# con-right-bot.net
KiCad netlist of a schematic drawn in Altium Designer
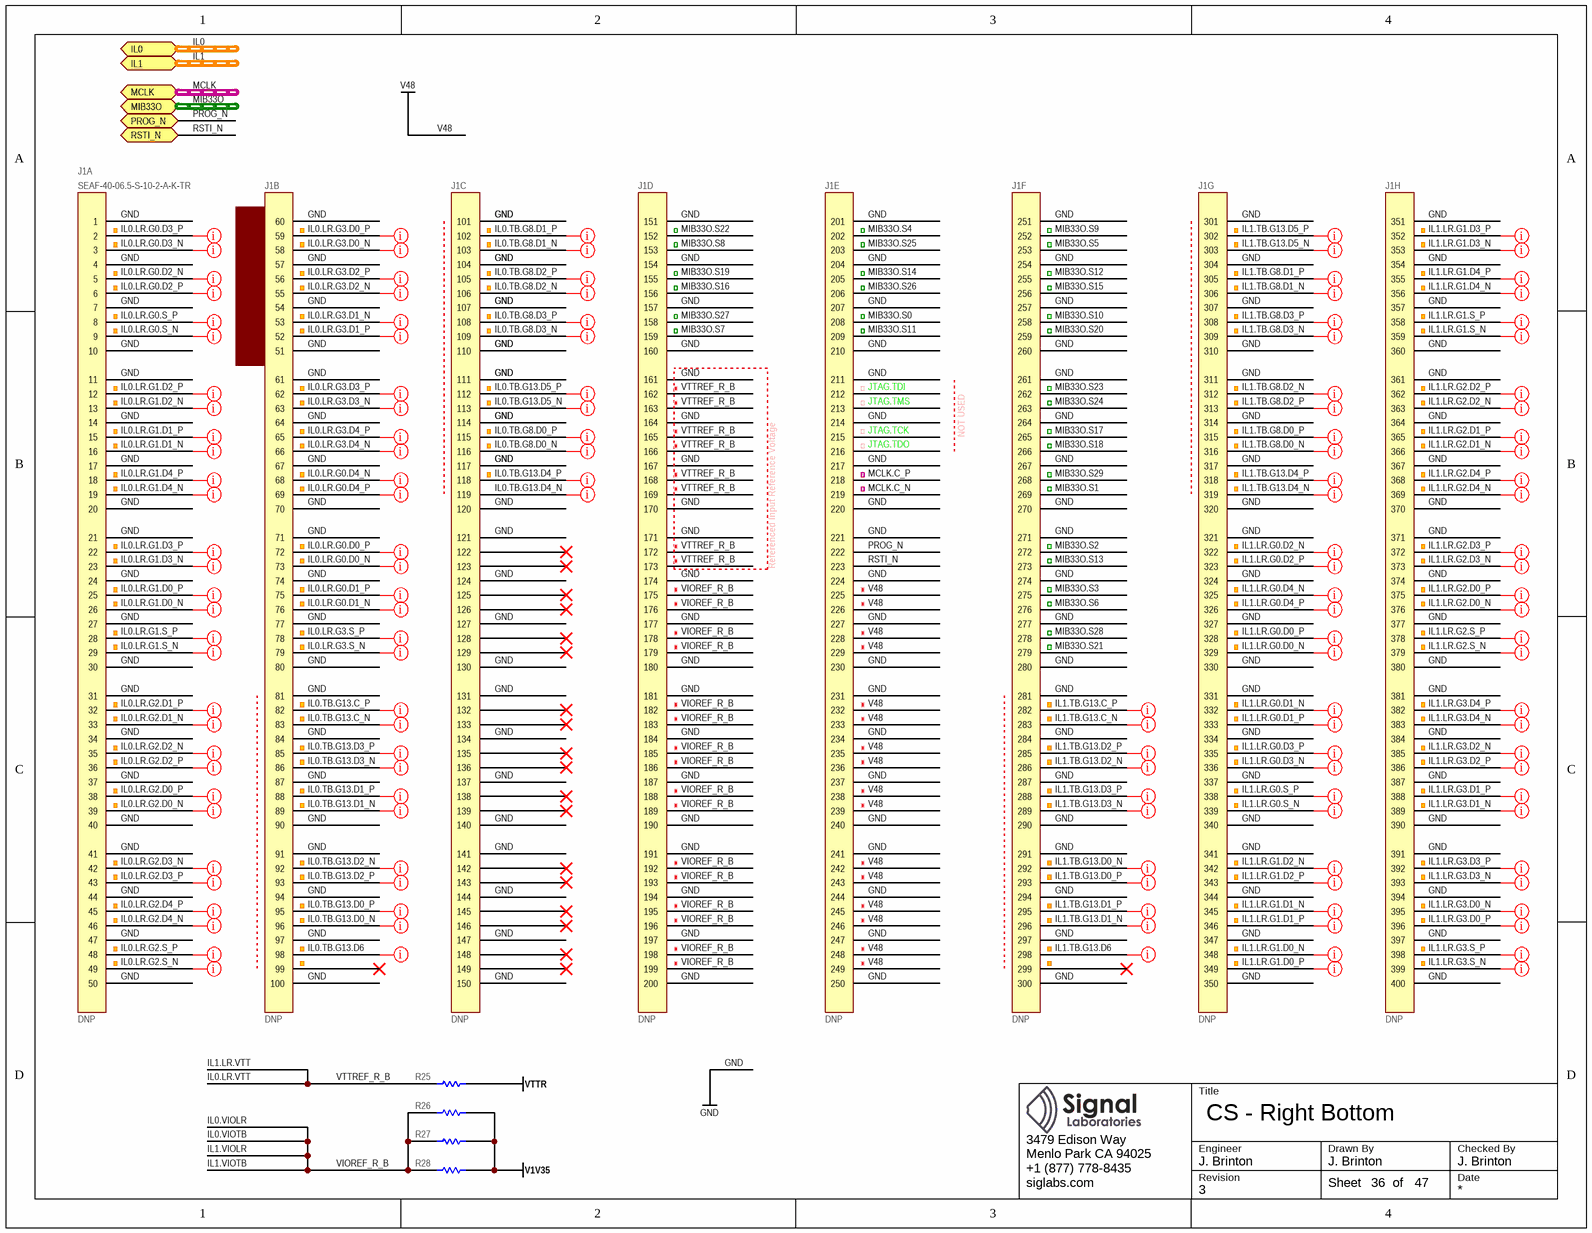
[diagram p0: con-right-bot.SchDoc]

(export (version "E")
  (design (tool "Eeschema 10.0.6"))
  (components
    (comp (ref "J1")
      (value "SEAF-40-06.5-S-10-2-A-K-TR")
      (footprint "samtec:SEAF-40-06.5-S-10-2-A-K-TR")
      (description "Terminal Array Assembly, Surface Mount, 0.050\" Pitch, 400 Pins")
      (fields (field (name "MANUFACTURER") "Samtec") (field (name "DO NOT PLACE") "DNP"))
      (libsource (lib "samtec") (part "SEAF-40-06.5-S-10-2-A-K-TR"))
    )
    (comp (ref "R25")
      (value "SOLDER_LINK")
      (footprint "SOLDERLINK0603X26N")
      (description "Solder Link")
      (libsource (lib "generic") (part "RES"))
    )
    (comp (ref "R26")
      (value "SOLDER_LINK")
      (footprint "SOLDERLINK0603X26N")
      (description "Solder Link")
      (libsource (lib "generic") (part "RES"))
    )
    (comp (ref "R27")
      (value "SOLDER_LINK")
      (footprint "SOLDERLINK0603X26N")
      (description "Solder Link")
      (libsource (lib "generic") (part "RES"))
    )
    (comp (ref "R28")
      (value "SOLDER_LINK")
      (footprint "SOLDERLINK0603X26N")
      (description "Solder Link")
      (libsource (lib "generic") (part "RES"))
    )
  )
  (nets
    (net (code "5") (name "/IL0.LR.G0.D0_N") (class "Default")
      (node (ref "J1") (pin "73") (pinfunction "73_73") (pintype "passive"))
    )
    (net (code "6") (name "/IL0.LR.G0.D0_P") (class "Default")
      (node (ref "J1") (pin "72") (pinfunction "72_72") (pintype "passive"))
    )
    (net (code "7") (name "/IL0.LR.G0.D1_N") (class "Default")
      (node (ref "J1") (pin "76") (pinfunction "76_76") (pintype "passive"))
    )
    (net (code "8") (name "/IL0.LR.G0.D1_P") (class "Default")
      (node (ref "J1") (pin "75") (pinfunction "75_75") (pintype "passive"))
    )
    (net (code "9") (name "/IL0.LR.G0.D2_N") (class "Default")
      (node (ref "J1") (pin "5") (pinfunction "5_5") (pintype "passive"))
    )
    (net (code "10") (name "/IL0.LR.G0.D2_P") (class "Default")
      (node (ref "J1") (pin "6") (pinfunction "6_6") (pintype "passive"))
    )
    (net (code "11") (name "/IL0.LR.G0.D3_N") (class "Default")
      (node (ref "J1") (pin "3") (pinfunction "3_3") (pintype "passive"))
    )
    (net (code "12") (name "/IL0.LR.G0.D3_P") (class "Default")
      (node (ref "J1") (pin "2") (pinfunction "2_2") (pintype "passive"))
    )
    (net (code "13") (name "/IL0.LR.G0.D4_N") (class "Default")
      (node (ref "J1") (pin "68") (pinfunction "68_68") (pintype "passive"))
    )
    (net (code "14") (name "/IL0.LR.G0.D4_P") (class "Default")
      (node (ref "J1") (pin "69") (pinfunction "69_69") (pintype "passive"))
    )
    (net (code "15") (name "/IL0.LR.G0.S_N") (class "Default")
      (node (ref "J1") (pin "9") (pinfunction "9_9") (pintype "passive"))
    )
    (net (code "16") (name "/IL0.LR.G0.S_P") (class "Default")
      (node (ref "J1") (pin "8") (pinfunction "8_8") (pintype "passive"))
    )
    (net (code "17") (name "/IL0.LR.G1.D0_N") (class "Default")
      (node (ref "J1") (pin "26") (pinfunction "26_26") (pintype "passive"))
    )
    (net (code "18") (name "/IL0.LR.G1.D0_P") (class "Default")
      (node (ref "J1") (pin "25") (pinfunction "25_25") (pintype "passive"))
    )
    (net (code "19") (name "/IL0.LR.G1.D1_N") (class "Default")
      (node (ref "J1") (pin "16") (pinfunction "16_16") (pintype "passive"))
    )
    (net (code "20") (name "/IL0.LR.G1.D1_P") (class "Default")
      (node (ref "J1") (pin "15") (pinfunction "15_15") (pintype "passive"))
    )
    (net (code "21") (name "/IL0.LR.G1.D2_N") (class "Default")
      (node (ref "J1") (pin "13") (pinfunction "13_13") (pintype "passive"))
    )
    (net (code "22") (name "/IL0.LR.G1.D2_P") (class "Default")
      (node (ref "J1") (pin "12") (pinfunction "12_12") (pintype "passive"))
    )
    (net (code "23") (name "/IL0.LR.G1.D3_N") (class "Default")
      (node (ref "J1") (pin "23") (pinfunction "23_23") (pintype "passive"))
    )
    (net (code "24") (name "/IL0.LR.G1.D3_P") (class "Default")
      (node (ref "J1") (pin "22") (pinfunction "22_22") (pintype "passive"))
    )
    (net (code "25") (name "/IL0.LR.G1.D4_N") (class "Default")
      (node (ref "J1") (pin "19") (pinfunction "19_19") (pintype "passive"))
    )
    (net (code "26") (name "/IL0.LR.G1.D4_P") (class "Default")
      (node (ref "J1") (pin "18") (pinfunction "18_18") (pintype "passive"))
    )
    (net (code "27") (name "/IL0.LR.G1.S_N") (class "Default")
      (node (ref "J1") (pin "29") (pinfunction "29_29") (pintype "passive"))
    )
    (net (code "28") (name "/IL0.LR.G1.S_P") (class "Default")
      (node (ref "J1") (pin "28") (pinfunction "28_28") (pintype "passive"))
    )
    (net (code "29") (name "/IL0.LR.G2.D0_N") (class "Default")
      (node (ref "J1") (pin "39") (pinfunction "39_39") (pintype "passive"))
    )
    (net (code "30") (name "/IL0.LR.G2.D0_P") (class "Default")
      (node (ref "J1") (pin "38") (pinfunction "38_38") (pintype "passive"))
    )
    (net (code "31") (name "/IL0.LR.G2.D1_N") (class "Default")
      (node (ref "J1") (pin "33") (pinfunction "33_33") (pintype "passive"))
    )
    (net (code "32") (name "/IL0.LR.G2.D1_P") (class "Default")
      (node (ref "J1") (pin "32") (pinfunction "32_32") (pintype "passive"))
    )
    (net (code "33") (name "/IL0.LR.G2.D2_N") (class "Default")
      (node (ref "J1") (pin "35") (pinfunction "35_35") (pintype "passive"))
    )
    (net (code "34") (name "/IL0.LR.G2.D2_P") (class "Default")
      (node (ref "J1") (pin "36") (pinfunction "36_36") (pintype "passive"))
    )
    (net (code "35") (name "/IL0.LR.G2.D3_N") (class "Default")
      (node (ref "J1") (pin "42") (pinfunction "42_42") (pintype "passive"))
    )
    (net (code "36") (name "/IL0.LR.G2.D3_P") (class "Default")
      (node (ref "J1") (pin "43") (pinfunction "43_43") (pintype "passive"))
    )
    (net (code "37") (name "/IL0.LR.G2.D4_N") (class "Default")
      (node (ref "J1") (pin "46") (pinfunction "46_46") (pintype "passive"))
    )
    (net (code "38") (name "/IL0.LR.G2.D4_P") (class "Default")
      (node (ref "J1") (pin "45") (pinfunction "45_45") (pintype "passive"))
    )
    (net (code "39") (name "/IL0.LR.G2.S_N") (class "Default")
      (node (ref "J1") (pin "49") (pinfunction "49_49") (pintype "passive"))
    )
    (net (code "40") (name "/IL0.LR.G2.S_P") (class "Default")
      (node (ref "J1") (pin "48") (pinfunction "48_48") (pintype "passive"))
    )
    (net (code "41") (name "/IL0.LR.G3.D0_N") (class "Default")
      (node (ref "J1") (pin "58") (pinfunction "58_58") (pintype "passive"))
    )
    (net (code "42") (name "/IL0.LR.G3.D0_P") (class "Default")
      (node (ref "J1") (pin "59") (pinfunction "59_59") (pintype "passive"))
    )
    (net (code "43") (name "/IL0.LR.G3.D1_N") (class "Default")
      (node (ref "J1") (pin "53") (pinfunction "53_53") (pintype "passive"))
    )
    (net (code "44") (name "/IL0.LR.G3.D1_P") (class "Default")
      (node (ref "J1") (pin "52") (pinfunction "52_52") (pintype "passive"))
    )
    (net (code "45") (name "/IL0.LR.G3.D2_N") (class "Default")
      (node (ref "J1") (pin "55") (pinfunction "55_55") (pintype "passive"))
    )
    (net (code "46") (name "/IL0.LR.G3.D2_P") (class "Default")
      (node (ref "J1") (pin "56") (pinfunction "56_56") (pintype "passive"))
    )
    (net (code "47") (name "/IL0.LR.G3.D3_N") (class "Default")
      (node (ref "J1") (pin "63") (pinfunction "63_63") (pintype "passive"))
    )
    (net (code "48") (name "/IL0.LR.G3.D3_P") (class "Default")
      (node (ref "J1") (pin "62") (pinfunction "62_62") (pintype "passive"))
    )
    (net (code "49") (name "/IL0.LR.G3.D4_N") (class "Default")
      (node (ref "J1") (pin "66") (pinfunction "66_66") (pintype "passive"))
    )
    (net (code "50") (name "/IL0.LR.G3.D4_P") (class "Default")
      (node (ref "J1") (pin "65") (pinfunction "65_65") (pintype "passive"))
    )
    (net (code "51") (name "/IL0.LR.G3.S_N") (class "Default")
      (node (ref "J1") (pin "79") (pinfunction "79_79") (pintype "passive"))
    )
    (net (code "52") (name "/IL0.LR.G3.S_P") (class "Default")
      (node (ref "J1") (pin "78") (pinfunction "78_78") (pintype "passive"))
    )
    (net (code "53") (name "/IL0.LR.VTT") (class "Default")
      (node (ref "J1") (pin "162") (pinfunction "162_162") (pintype "passive"))
      (node (ref "J1") (pin "163") (pinfunction "163_163") (pintype "passive"))
      (node (ref "J1") (pin "165") (pinfunction "165_165") (pintype "passive"))
      (node (ref "J1") (pin "166") (pinfunction "166_166") (pintype "passive"))
      (node (ref "J1") (pin "168") (pinfunction "168_168") (pintype "passive"))
      (node (ref "J1") (pin "169") (pinfunction "169_169") (pintype "passive"))
      (node (ref "J1") (pin "172") (pinfunction "172_172") (pintype "passive"))
      (node (ref "J1") (pin "173") (pinfunction "173_173") (pintype "passive"))
      (node (ref "R25") (pin "2") (pinfunction "2_2") (pintype "passive"))
    )
    (net (code "54") (name "/IL0.TB.G8.D0_N") (class "Default")
      (node (ref "J1") (pin "116") (pinfunction "116_116") (pintype "passive"))
    )
    (net (code "55") (name "/IL0.TB.G8.D0_P") (class "Default")
      (node (ref "J1") (pin "115") (pinfunction "115_115") (pintype "passive"))
    )
    (net (code "56") (name "/IL0.TB.G8.D1_N") (class "Default")
      (node (ref "J1") (pin "103") (pinfunction "103_103") (pintype "passive"))
    )
    (net (code "57") (name "/IL0.TB.G8.D1_P") (class "Default")
      (node (ref "J1") (pin "102") (pinfunction "102_102") (pintype "passive"))
    )
    (net (code "58") (name "/IL0.TB.G8.D2_N") (class "Default")
      (node (ref "J1") (pin "106") (pinfunction "106_106") (pintype "passive"))
    )
    (net (code "59") (name "/IL0.TB.G8.D2_P") (class "Default")
      (node (ref "J1") (pin "105") (pinfunction "105_105") (pintype "passive"))
    )
    (net (code "60") (name "/IL0.TB.G8.D3_N") (class "Default")
      (node (ref "J1") (pin "109") (pinfunction "109_109") (pintype "passive"))
    )
    (net (code "61") (name "/IL0.TB.G8.D3_P") (class "Default")
      (node (ref "J1") (pin "108") (pinfunction "108_108") (pintype "passive"))
    )
    (net (code "62") (name "/IL0.TB.G13.C_N") (class "Default")
      (node (ref "J1") (pin "83") (pinfunction "83_83") (pintype "passive"))
    )
    (net (code "63") (name "/IL0.TB.G13.C_P") (class "Default")
      (node (ref "J1") (pin "82") (pinfunction "82_82") (pintype "passive"))
    )
    (net (code "64") (name "/IL0.TB.G13.D0_N") (class "Default")
      (node (ref "J1") (pin "96") (pinfunction "96_96") (pintype "passive"))
    )
    (net (code "65") (name "/IL0.TB.G13.D0_P") (class "Default")
      (node (ref "J1") (pin "95") (pinfunction "95_95") (pintype "passive"))
    )
    (net (code "66") (name "/IL0.TB.G13.D1_N") (class "Default")
      (node (ref "J1") (pin "89") (pinfunction "89_89") (pintype "passive"))
    )
    (net (code "67") (name "/IL0.TB.G13.D1_P") (class "Default")
      (node (ref "J1") (pin "88") (pinfunction "88_88") (pintype "passive"))
    )
    (net (code "68") (name "/IL0.TB.G13.D2_N") (class "Default")
      (node (ref "J1") (pin "92") (pinfunction "92_92") (pintype "passive"))
    )
    (net (code "69") (name "/IL0.TB.G13.D2_P") (class "Default")
      (node (ref "J1") (pin "93") (pinfunction "93_93") (pintype "passive"))
    )
    (net (code "70") (name "/IL0.TB.G13.D3_N") (class "Default")
      (node (ref "J1") (pin "86") (pinfunction "86_86") (pintype "passive"))
    )
    (net (code "71") (name "/IL0.TB.G13.D3_P") (class "Default")
      (node (ref "J1") (pin "85") (pinfunction "85_85") (pintype "passive"))
    )
    (net (code "72") (name "/IL0.TB.G13.D4_N") (class "Default")
      (node (ref "J1") (pin "119") (pinfunction "119_119") (pintype "passive"))
    )
    (net (code "73") (name "/IL0.TB.G13.D4_P") (class "Default")
      (node (ref "J1") (pin "118") (pinfunction "118_118") (pintype "passive"))
    )
    (net (code "74") (name "/IL0.TB.G13.D5_N") (class "Default")
      (node (ref "J1") (pin "113") (pinfunction "113_113") (pintype "passive"))
    )
    (net (code "75") (name "/IL0.TB.G13.D5_P") (class "Default")
      (node (ref "J1") (pin "112") (pinfunction "112_112") (pintype "passive"))
    )
    (net (code "76") (name "/IL0.TB.G13.D6") (class "Default")
      (node (ref "J1") (pin "98") (pinfunction "98_98") (pintype "passive"))
    )
    (net (code "77") (name "/IL0.VIOLR") (class "Default")
      (node (ref "J1") (pin "175") (pinfunction "175_175") (pintype "passive"))
      (node (ref "J1") (pin "176") (pinfunction "176_176") (pintype "passive"))
      (node (ref "J1") (pin "178") (pinfunction "178_178") (pintype "passive"))
      (node (ref "J1") (pin "179") (pinfunction "179_179") (pintype "passive"))
      (node (ref "J1") (pin "182") (pinfunction "182_182") (pintype "passive"))
      (node (ref "J1") (pin "183") (pinfunction "183_183") (pintype "passive"))
      (node (ref "J1") (pin "185") (pinfunction "185_185") (pintype "passive"))
      (node (ref "J1") (pin "186") (pinfunction "186_186") (pintype "passive"))
      (node (ref "J1") (pin "188") (pinfunction "188_188") (pintype "passive"))
      (node (ref "J1") (pin "189") (pinfunction "189_189") (pintype "passive"))
      (node (ref "J1") (pin "192") (pinfunction "192_192") (pintype "passive"))
      (node (ref "J1") (pin "193") (pinfunction "193_193") (pintype "passive"))
      (node (ref "J1") (pin "195") (pinfunction "195_195") (pintype "passive"))
      (node (ref "J1") (pin "196") (pinfunction "196_196") (pintype "passive"))
      (node (ref "J1") (pin "198") (pinfunction "198_198") (pintype "passive"))
      (node (ref "J1") (pin "199") (pinfunction "199_199") (pintype "passive"))
      (node (ref "R26") (pin "2") (pinfunction "2_2") (pintype "passive"))
      (node (ref "R27") (pin "2") (pinfunction "2_2") (pintype "passive"))
      (node (ref "R28") (pin "2") (pinfunction "2_2") (pintype "passive"))
    )
    (net (code "78") (name "/IL1.LR.G0.D0_N") (class "Default")
      (node (ref "J1") (pin "329") (pinfunction "329_329") (pintype "passive"))
    )
    (net (code "79") (name "/IL1.LR.G0.D0_P") (class "Default")
      (node (ref "J1") (pin "328") (pinfunction "328_328") (pintype "passive"))
    )
    (net (code "80") (name "/IL1.LR.G0.D1_N") (class "Default")
      (node (ref "J1") (pin "332") (pinfunction "332_332") (pintype "passive"))
    )
    (net (code "81") (name "/IL1.LR.G0.D1_P") (class "Default")
      (node (ref "J1") (pin "333") (pinfunction "333_333") (pintype "passive"))
    )
    (net (code "82") (name "/IL1.LR.G0.D2_N") (class "Default")
      (node (ref "J1") (pin "322") (pinfunction "322_322") (pintype "passive"))
    )
    (net (code "83") (name "/IL1.LR.G0.D2_P") (class "Default")
      (node (ref "J1") (pin "323") (pinfunction "323_323") (pintype "passive"))
    )
    (net (code "84") (name "/IL1.LR.G0.D3_N") (class "Default")
      (node (ref "J1") (pin "336") (pinfunction "336_336") (pintype "passive"))
    )
    (net (code "85") (name "/IL1.LR.G0.D3_P") (class "Default")
      (node (ref "J1") (pin "335") (pinfunction "335_335") (pintype "passive"))
    )
    (net (code "86") (name "/IL1.LR.G0.D4_N") (class "Default")
      (node (ref "J1") (pin "325") (pinfunction "325_325") (pintype "passive"))
    )
    (net (code "87") (name "/IL1.LR.G0.D4_P") (class "Default")
      (node (ref "J1") (pin "326") (pinfunction "326_326") (pintype "passive"))
    )
    (net (code "88") (name "/IL1.LR.G0.S_N") (class "Default")
      (node (ref "J1") (pin "339") (pinfunction "339_339") (pintype "passive"))
    )
    (net (code "89") (name "/IL1.LR.G0.S_P") (class "Default")
      (node (ref "J1") (pin "338") (pinfunction "338_338") (pintype "passive"))
    )
    (net (code "90") (name "/IL1.LR.G1.D0_N") (class "Default")
      (node (ref "J1") (pin "348") (pinfunction "348_348") (pintype "passive"))
    )
    (net (code "91") (name "/IL1.LR.G1.D0_P") (class "Default")
      (node (ref "J1") (pin "349") (pinfunction "349_349") (pintype "passive"))
    )
    (net (code "92") (name "/IL1.LR.G1.D1_N") (class "Default")
      (node (ref "J1") (pin "345") (pinfunction "345_345") (pintype "passive"))
    )
    (net (code "93") (name "/IL1.LR.G1.D1_P") (class "Default")
      (node (ref "J1") (pin "346") (pinfunction "346_346") (pintype "passive"))
    )
    (net (code "94") (name "/IL1.LR.G1.D2_N") (class "Default")
      (node (ref "J1") (pin "342") (pinfunction "342_342") (pintype "passive"))
    )
    (net (code "95") (name "/IL1.LR.G1.D2_P") (class "Default")
      (node (ref "J1") (pin "343") (pinfunction "343_343") (pintype "passive"))
    )
    (net (code "96") (name "/IL1.LR.G1.D3_N") (class "Default")
      (node (ref "J1") (pin "353") (pinfunction "353_353") (pintype "passive"))
    )
    (net (code "97") (name "/IL1.LR.G1.D3_P") (class "Default")
      (node (ref "J1") (pin "352") (pinfunction "352_352") (pintype "passive"))
    )
    (net (code "98") (name "/IL1.LR.G1.D4_N") (class "Default")
      (node (ref "J1") (pin "356") (pinfunction "356_356") (pintype "passive"))
    )
    (net (code "99") (name "/IL1.LR.G1.D4_P") (class "Default")
      (node (ref "J1") (pin "355") (pinfunction "355_355") (pintype "passive"))
    )
    (net (code "100") (name "/IL1.LR.G1.S_N") (class "Default")
      (node (ref "J1") (pin "359") (pinfunction "359_359") (pintype "passive"))
    )
    (net (code "101") (name "/IL1.LR.G1.S_P") (class "Default")
      (node (ref "J1") (pin "358") (pinfunction "358_358") (pintype "passive"))
    )
    (net (code "102") (name "/IL1.LR.G2.D0_N") (class "Default")
      (node (ref "J1") (pin "376") (pinfunction "376_376") (pintype "passive"))
    )
    (net (code "103") (name "/IL1.LR.G2.D0_P") (class "Default")
      (node (ref "J1") (pin "375") (pinfunction "375_375") (pintype "passive"))
    )
    (net (code "104") (name "/IL1.LR.G2.D1_N") (class "Default")
      (node (ref "J1") (pin "366") (pinfunction "366_366") (pintype "passive"))
    )
    (net (code "105") (name "/IL1.LR.G2.D1_P") (class "Default")
      (node (ref "J1") (pin "365") (pinfunction "365_365") (pintype "passive"))
    )
    (net (code "106") (name "/IL1.LR.G2.D2_N") (class "Default")
      (node (ref "J1") (pin "363") (pinfunction "363_363") (pintype "passive"))
    )
    (net (code "107") (name "/IL1.LR.G2.D2_P") (class "Default")
      (node (ref "J1") (pin "362") (pinfunction "362_362") (pintype "passive"))
    )
    (net (code "108") (name "/IL1.LR.G2.D3_N") (class "Default")
      (node (ref "J1") (pin "373") (pinfunction "373_373") (pintype "passive"))
    )
    (net (code "109") (name "/IL1.LR.G2.D3_P") (class "Default")
      (node (ref "J1") (pin "372") (pinfunction "372_372") (pintype "passive"))
    )
    (net (code "110") (name "/IL1.LR.G2.D4_N") (class "Default")
      (node (ref "J1") (pin "369") (pinfunction "369_369") (pintype "passive"))
    )
    (net (code "111") (name "/IL1.LR.G2.D4_P") (class "Default")
      (node (ref "J1") (pin "368") (pinfunction "368_368") (pintype "passive"))
    )
    (net (code "112") (name "/IL1.LR.G2.S_N") (class "Default")
      (node (ref "J1") (pin "379") (pinfunction "379_379") (pintype "passive"))
    )
    (net (code "113") (name "/IL1.LR.G2.S_P") (class "Default")
      (node (ref "J1") (pin "378") (pinfunction "378_378") (pintype "passive"))
    )
    (net (code "114") (name "/IL1.LR.G3.D0_N") (class "Default")
      (node (ref "J1") (pin "395") (pinfunction "395_395") (pintype "passive"))
    )
    (net (code "115") (name "/IL1.LR.G3.D0_P") (class "Default")
      (node (ref "J1") (pin "396") (pinfunction "396_396") (pintype "passive"))
    )
    (net (code "116") (name "/IL1.LR.G3.D1_N") (class "Default")
      (node (ref "J1") (pin "389") (pinfunction "389_389") (pintype "passive"))
    )
    (net (code "117") (name "/IL1.LR.G3.D1_P") (class "Default")
      (node (ref "J1") (pin "388") (pinfunction "388_388") (pintype "passive"))
    )
    (net (code "118") (name "/IL1.LR.G3.D2_N") (class "Default")
      (node (ref "J1") (pin "385") (pinfunction "385_385") (pintype "passive"))
    )
    (net (code "119") (name "/IL1.LR.G3.D2_P") (class "Default")
      (node (ref "J1") (pin "386") (pinfunction "386_386") (pintype "passive"))
    )
    (net (code "120") (name "/IL1.LR.G3.D3_N") (class "Default")
      (node (ref "J1") (pin "393") (pinfunction "393_393") (pintype "passive"))
    )
    (net (code "121") (name "/IL1.LR.G3.D3_P") (class "Default")
      (node (ref "J1") (pin "392") (pinfunction "392_392") (pintype "passive"))
    )
    (net (code "122") (name "/IL1.LR.G3.D4_N") (class "Default")
      (node (ref "J1") (pin "383") (pinfunction "383_383") (pintype "passive"))
    )
    (net (code "123") (name "/IL1.LR.G3.D4_P") (class "Default")
      (node (ref "J1") (pin "382") (pinfunction "382_382") (pintype "passive"))
    )
    (net (code "124") (name "/IL1.LR.G3.S_N") (class "Default")
      (node (ref "J1") (pin "399") (pinfunction "399_399") (pintype "passive"))
    )
    (net (code "125") (name "/IL1.LR.G3.S_P") (class "Default")
      (node (ref "J1") (pin "398") (pinfunction "398_398") (pintype "passive"))
    )
    (net (code "126") (name "/IL1.TB.G8.D0_N") (class "Default")
      (node (ref "J1") (pin "316") (pinfunction "316_316") (pintype "passive"))
    )
    (net (code "127") (name "/IL1.TB.G8.D0_P") (class "Default")
      (node (ref "J1") (pin "315") (pinfunction "315_315") (pintype "passive"))
    )
    (net (code "128") (name "/IL1.TB.G8.D1_N") (class "Default")
      (node (ref "J1") (pin "306") (pinfunction "306_306") (pintype "passive"))
    )
    (net (code "129") (name "/IL1.TB.G8.D1_P") (class "Default")
      (node (ref "J1") (pin "305") (pinfunction "305_305") (pintype "passive"))
    )
    (net (code "130") (name "/IL1.TB.G8.D2_N") (class "Default")
      (node (ref "J1") (pin "312") (pinfunction "312_312") (pintype "passive"))
    )
    (net (code "131") (name "/IL1.TB.G8.D2_P") (class "Default")
      (node (ref "J1") (pin "313") (pinfunction "313_313") (pintype "passive"))
    )
    (net (code "132") (name "/IL1.TB.G8.D3_N") (class "Default")
      (node (ref "J1") (pin "309") (pinfunction "309_309") (pintype "passive"))
    )
    (net (code "133") (name "/IL1.TB.G8.D3_P") (class "Default")
      (node (ref "J1") (pin "308") (pinfunction "308_308") (pintype "passive"))
    )
    (net (code "134") (name "/IL1.TB.G13.C_N") (class "Default")
      (node (ref "J1") (pin "283") (pinfunction "283_283") (pintype "passive"))
    )
    (net (code "135") (name "/IL1.TB.G13.C_P") (class "Default")
      (node (ref "J1") (pin "282") (pinfunction "282_282") (pintype "passive"))
    )
    (net (code "136") (name "/IL1.TB.G13.D0_N") (class "Default")
      (node (ref "J1") (pin "292") (pinfunction "292_292") (pintype "passive"))
    )
    (net (code "137") (name "/IL1.TB.G13.D0_P") (class "Default")
      (node (ref "J1") (pin "293") (pinfunction "293_293") (pintype "passive"))
    )
    (net (code "138") (name "/IL1.TB.G13.D1_N") (class "Default")
      (node (ref "J1") (pin "296") (pinfunction "296_296") (pintype "passive"))
    )
    (net (code "139") (name "/IL1.TB.G13.D1_P") (class "Default")
      (node (ref "J1") (pin "295") (pinfunction "295_295") (pintype "passive"))
    )
    (net (code "140") (name "/IL1.TB.G13.D2_N") (class "Default")
      (node (ref "J1") (pin "286") (pinfunction "286_286") (pintype "passive"))
    )
    (net (code "141") (name "/IL1.TB.G13.D2_P") (class "Default")
      (node (ref "J1") (pin "285") (pinfunction "285_285") (pintype "passive"))
    )
    (net (code "142") (name "/IL1.TB.G13.D3_N") (class "Default")
      (node (ref "J1") (pin "289") (pinfunction "289_289") (pintype "passive"))
    )
    (net (code "143") (name "/IL1.TB.G13.D3_P") (class "Default")
      (node (ref "J1") (pin "288") (pinfunction "288_288") (pintype "passive"))
    )
    (net (code "144") (name "/IL1.TB.G13.D4_N") (class "Default")
      (node (ref "J1") (pin "319") (pinfunction "319_319") (pintype "passive"))
    )
    (net (code "145") (name "/IL1.TB.G13.D4_P") (class "Default")
      (node (ref "J1") (pin "318") (pinfunction "318_318") (pintype "passive"))
    )
    (net (code "146") (name "/IL1.TB.G13.D5_N") (class "Default")
      (node (ref "J1") (pin "303") (pinfunction "303_303") (pintype "passive"))
    )
    (net (code "147") (name "/IL1.TB.G13.D5_P") (class "Default")
      (node (ref "J1") (pin "302") (pinfunction "302_302") (pintype "passive"))
    )
    (net (code "148") (name "/IL1.TB.G13.D6") (class "Default")
      (node (ref "J1") (pin "298") (pinfunction "298_298") (pintype "passive"))
    )
    (net (code "149") (name "/MCLK.C_N") (class "Default")
      (node (ref "J1") (pin "219") (pinfunction "219_219") (pintype "passive"))
    )
    (net (code "150") (name "/MCLK.C_P") (class "Default")
      (node (ref "J1") (pin "218") (pinfunction "218_218") (pintype "passive"))
    )
    (net (code "151") (name "/MIB33O.S0") (class "Default")
      (node (ref "J1") (pin "208") (pinfunction "208_208") (pintype "passive"))
    )
    (net (code "152") (name "/MIB33O.S1") (class "Default")
      (node (ref "J1") (pin "269") (pinfunction "269_269") (pintype "passive"))
    )
    (net (code "153") (name "/MIB33O.S2") (class "Default")
      (node (ref "J1") (pin "272") (pinfunction "272_272") (pintype "passive"))
    )
    (net (code "154") (name "/MIB33O.S3") (class "Default")
      (node (ref "J1") (pin "275") (pinfunction "275_275") (pintype "passive"))
    )
    (net (code "155") (name "/MIB33O.S4") (class "Default")
      (node (ref "J1") (pin "202") (pinfunction "202_202") (pintype "passive"))
    )
    (net (code "156") (name "/MIB33O.S5") (class "Default")
      (node (ref "J1") (pin "253") (pinfunction "253_253") (pintype "passive"))
    )
    (net (code "157") (name "/MIB33O.S6") (class "Default")
      (node (ref "J1") (pin "276") (pinfunction "276_276") (pintype "passive"))
    )
    (net (code "158") (name "/MIB33O.S7") (class "Default")
      (node (ref "J1") (pin "159") (pinfunction "159_159") (pintype "passive"))
    )
    (net (code "159") (name "/MIB33O.S8") (class "Default")
      (node (ref "J1") (pin "153") (pinfunction "153_153") (pintype "passive"))
    )
    (net (code "160") (name "/MIB33O.S9") (class "Default")
      (node (ref "J1") (pin "252") (pinfunction "252_252") (pintype "passive"))
    )
    (net (code "161") (name "/MIB33O.S10") (class "Default")
      (node (ref "J1") (pin "258") (pinfunction "258_258") (pintype "passive"))
    )
    (net (code "162") (name "/MIB33O.S11") (class "Default")
      (node (ref "J1") (pin "209") (pinfunction "209_209") (pintype "passive"))
    )
    (net (code "163") (name "/MIB33O.S12") (class "Default")
      (node (ref "J1") (pin "255") (pinfunction "255_255") (pintype "passive"))
    )
    (net (code "164") (name "/MIB33O.S13") (class "Default")
      (node (ref "J1") (pin "273") (pinfunction "273_273") (pintype "passive"))
    )
    (net (code "165") (name "/MIB33O.S14") (class "Default")
      (node (ref "J1") (pin "205") (pinfunction "205_205") (pintype "passive"))
    )
    (net (code "166") (name "/MIB33O.S15") (class "Default")
      (node (ref "J1") (pin "256") (pinfunction "256_256") (pintype "passive"))
    )
    (net (code "167") (name "/MIB33O.S16") (class "Default")
      (node (ref "J1") (pin "156") (pinfunction "156_156") (pintype "passive"))
    )
    (net (code "168") (name "/MIB33O.S17") (class "Default")
      (node (ref "J1") (pin "265") (pinfunction "265_265") (pintype "passive"))
    )
    (net (code "169") (name "/MIB33O.S18") (class "Default")
      (node (ref "J1") (pin "266") (pinfunction "266_266") (pintype "passive"))
    )
    (net (code "170") (name "/MIB33O.S19") (class "Default")
      (node (ref "J1") (pin "155") (pinfunction "155_155") (pintype "passive"))
    )
    (net (code "171") (name "/MIB33O.S20") (class "Default")
      (node (ref "J1") (pin "259") (pinfunction "259_259") (pintype "passive"))
    )
    (net (code "172") (name "/MIB33O.S21") (class "Default")
      (node (ref "J1") (pin "279") (pinfunction "279_279") (pintype "passive"))
    )
    (net (code "173") (name "/MIB33O.S22") (class "Default")
      (node (ref "J1") (pin "152") (pinfunction "152_152") (pintype "passive"))
    )
    (net (code "174") (name "/MIB33O.S23") (class "Default")
      (node (ref "J1") (pin "262") (pinfunction "262_262") (pintype "passive"))
    )
    (net (code "175") (name "/MIB33O.S24") (class "Default")
      (node (ref "J1") (pin "263") (pinfunction "263_263") (pintype "passive"))
    )
    (net (code "176") (name "/MIB33O.S25") (class "Default")
      (node (ref "J1") (pin "203") (pinfunction "203_203") (pintype "passive"))
    )
    (net (code "177") (name "/MIB33O.S26") (class "Default")
      (node (ref "J1") (pin "206") (pinfunction "206_206") (pintype "passive"))
    )
    (net (code "178") (name "/MIB33O.S27") (class "Default")
      (node (ref "J1") (pin "158") (pinfunction "158_158") (pintype "passive"))
    )
    (net (code "179") (name "/MIB33O.S28") (class "Default")
      (node (ref "J1") (pin "278") (pinfunction "278_278") (pintype "passive"))
    )
    (net (code "180") (name "/MIB33O.S29") (class "Default")
      (node (ref "J1") (pin "268") (pinfunction "268_268") (pintype "passive"))
    )
    (net (code "181") (name "/PROG_N") (class "Default")
      (node (ref "J1") (pin "222") (pinfunction "222_222") (pintype "passive"))
    )
    (net (code "182") (name "/RSTI_N") (class "Default")
      (node (ref "J1") (pin "223") (pinfunction "223_223") (pintype "passive"))
    )
    (net (code "187") (name "GND") (class "Default")
      (node (ref "J1") (pin "1") (pinfunction "1_1") (pintype "passive"))
      (node (ref "J1") (pin "10") (pinfunction "10_10") (pintype "passive"))
      (node (ref "J1") (pin "100") (pinfunction "100_100") (pintype "passive"))
      (node (ref "J1") (pin "101") (pinfunction "101_101") (pintype "passive"))
      (node (ref "J1") (pin "104") (pinfunction "104_104") (pintype "passive"))
      (node (ref "J1") (pin "107") (pinfunction "107_107") (pintype "passive"))
      (node (ref "J1") (pin "11") (pinfunction "11_11") (pintype "passive"))
      (node (ref "J1") (pin "110") (pinfunction "110_110") (pintype "passive"))
      (node (ref "J1") (pin "111") (pinfunction "111_111") (pintype "passive"))
      (node (ref "J1") (pin "114") (pinfunction "114_114") (pintype "passive"))
      (node (ref "J1") (pin "117") (pinfunction "117_117") (pintype "passive"))
      (node (ref "J1") (pin "120") (pinfunction "120_120") (pintype "passive"))
      (node (ref "J1") (pin "121") (pinfunction "121_121") (pintype "passive"))
      (node (ref "J1") (pin "124") (pinfunction "124_124") (pintype "passive"))
      (node (ref "J1") (pin "127") (pinfunction "127_127") (pintype "passive"))
      (node (ref "J1") (pin "130") (pinfunction "130_130") (pintype "passive"))
      (node (ref "J1") (pin "131") (pinfunction "131_131") (pintype "passive"))
      (node (ref "J1") (pin "134") (pinfunction "134_134") (pintype "passive"))
      (node (ref "J1") (pin "137") (pinfunction "137_137") (pintype "passive"))
      (node (ref "J1") (pin "14") (pinfunction "14_14") (pintype "passive"))
      (node (ref "J1") (pin "140") (pinfunction "140_140") (pintype "passive"))
      (node (ref "J1") (pin "141") (pinfunction "141_141") (pintype "passive"))
      (node (ref "J1") (pin "144") (pinfunction "144_144") (pintype "passive"))
      (node (ref "J1") (pin "147") (pinfunction "147_147") (pintype "passive"))
      (node (ref "J1") (pin "150") (pinfunction "150_150") (pintype "passive"))
      (node (ref "J1") (pin "151") (pinfunction "151_151") (pintype "passive"))
      (node (ref "J1") (pin "154") (pinfunction "154_154") (pintype "passive"))
      (node (ref "J1") (pin "157") (pinfunction "157_157") (pintype "passive"))
      (node (ref "J1") (pin "160") (pinfunction "160_160") (pintype "passive"))
      (node (ref "J1") (pin "161") (pinfunction "161_161") (pintype "passive"))
      (node (ref "J1") (pin "164") (pinfunction "164_164") (pintype "passive"))
      (node (ref "J1") (pin "167") (pinfunction "167_167") (pintype "passive"))
      (node (ref "J1") (pin "17") (pinfunction "17_17") (pintype "passive"))
      (node (ref "J1") (pin "170") (pinfunction "170_170") (pintype "passive"))
      (node (ref "J1") (pin "171") (pinfunction "171_171") (pintype "passive"))
      (node (ref "J1") (pin "174") (pinfunction "174_174") (pintype "passive"))
      (node (ref "J1") (pin "177") (pinfunction "177_177") (pintype "passive"))
      (node (ref "J1") (pin "180") (pinfunction "180_180") (pintype "passive"))
      (node (ref "J1") (pin "181") (pinfunction "181_181") (pintype "passive"))
      (node (ref "J1") (pin "184") (pinfunction "184_184") (pintype "passive"))
      (node (ref "J1") (pin "187") (pinfunction "187_187") (pintype "passive"))
      (node (ref "J1") (pin "190") (pinfunction "190_190") (pintype "passive"))
      (node (ref "J1") (pin "191") (pinfunction "191_191") (pintype "passive"))
      (node (ref "J1") (pin "194") (pinfunction "194_194") (pintype "passive"))
      (node (ref "J1") (pin "197") (pinfunction "197_197") (pintype "passive"))
      (node (ref "J1") (pin "20") (pinfunction "20_20") (pintype "passive"))
      (node (ref "J1") (pin "200") (pinfunction "200_200") (pintype "passive"))
      (node (ref "J1") (pin "201") (pinfunction "201_201") (pintype "passive"))
      (node (ref "J1") (pin "204") (pinfunction "204_204") (pintype "passive"))
      (node (ref "J1") (pin "207") (pinfunction "207_207") (pintype "passive"))
      (node (ref "J1") (pin "21") (pinfunction "21_21") (pintype "passive"))
      (node (ref "J1") (pin "210") (pinfunction "210_210") (pintype "passive"))
      (node (ref "J1") (pin "211") (pinfunction "211_211") (pintype "passive"))
      (node (ref "J1") (pin "214") (pinfunction "214_214") (pintype "passive"))
      (node (ref "J1") (pin "217") (pinfunction "217_217") (pintype "passive"))
      (node (ref "J1") (pin "220") (pinfunction "220_220") (pintype "passive"))
      (node (ref "J1") (pin "221") (pinfunction "221_221") (pintype "passive"))
      (node (ref "J1") (pin "224") (pinfunction "224_224") (pintype "passive"))
      (node (ref "J1") (pin "227") (pinfunction "227_227") (pintype "passive"))
      (node (ref "J1") (pin "230") (pinfunction "230_230") (pintype "passive"))
      (node (ref "J1") (pin "231") (pinfunction "231_231") (pintype "passive"))
      (node (ref "J1") (pin "234") (pinfunction "234_234") (pintype "passive"))
      (node (ref "J1") (pin "237") (pinfunction "237_237") (pintype "passive"))
      (node (ref "J1") (pin "24") (pinfunction "24_24") (pintype "passive"))
      (node (ref "J1") (pin "240") (pinfunction "240_240") (pintype "passive"))
      (node (ref "J1") (pin "241") (pinfunction "241_241") (pintype "passive"))
      (node (ref "J1") (pin "244") (pinfunction "244_244") (pintype "passive"))
      (node (ref "J1") (pin "247") (pinfunction "247_247") (pintype "passive"))
      (node (ref "J1") (pin "250") (pinfunction "250_250") (pintype "passive"))
      (node (ref "J1") (pin "251") (pinfunction "251_251") (pintype "passive"))
      (node (ref "J1") (pin "254") (pinfunction "254_254") (pintype "passive"))
      (node (ref "J1") (pin "257") (pinfunction "257_257") (pintype "passive"))
      (node (ref "J1") (pin "260") (pinfunction "260_260") (pintype "passive"))
      (node (ref "J1") (pin "261") (pinfunction "261_261") (pintype "passive"))
      (node (ref "J1") (pin "264") (pinfunction "264_264") (pintype "passive"))
      (node (ref "J1") (pin "267") (pinfunction "267_267") (pintype "passive"))
      (node (ref "J1") (pin "27") (pinfunction "27_27") (pintype "passive"))
      (node (ref "J1") (pin "270") (pinfunction "270_270") (pintype "passive"))
      (node (ref "J1") (pin "271") (pinfunction "271_271") (pintype "passive"))
      (node (ref "J1") (pin "274") (pinfunction "274_274") (pintype "passive"))
      (node (ref "J1") (pin "277") (pinfunction "277_277") (pintype "passive"))
      (node (ref "J1") (pin "280") (pinfunction "280_280") (pintype "passive"))
      (node (ref "J1") (pin "281") (pinfunction "281_281") (pintype "passive"))
      (node (ref "J1") (pin "284") (pinfunction "284_284") (pintype "passive"))
      (node (ref "J1") (pin "287") (pinfunction "287_287") (pintype "passive"))
      (node (ref "J1") (pin "290") (pinfunction "290_290") (pintype "passive"))
      (node (ref "J1") (pin "291") (pinfunction "291_291") (pintype "passive"))
      (node (ref "J1") (pin "294") (pinfunction "294_294") (pintype "passive"))
      (node (ref "J1") (pin "297") (pinfunction "297_297") (pintype "passive"))
      (node (ref "J1") (pin "30") (pinfunction "30_30") (pintype "passive"))
      (node (ref "J1") (pin "300") (pinfunction "300_300") (pintype "passive"))
      (node (ref "J1") (pin "301") (pinfunction "301_301") (pintype "passive"))
      (node (ref "J1") (pin "304") (pinfunction "304_304") (pintype "passive"))
      (node (ref "J1") (pin "307") (pinfunction "307_307") (pintype "passive"))
      (node (ref "J1") (pin "31") (pinfunction "31_31") (pintype "passive"))
      (node (ref "J1") (pin "310") (pinfunction "310_310") (pintype "passive"))
      (node (ref "J1") (pin "311") (pinfunction "311_311") (pintype "passive"))
      (node (ref "J1") (pin "314") (pinfunction "314_314") (pintype "passive"))
      (node (ref "J1") (pin "317") (pinfunction "317_317") (pintype "passive"))
      (node (ref "J1") (pin "320") (pinfunction "320_320") (pintype "passive"))
      (node (ref "J1") (pin "321") (pinfunction "321_321") (pintype "passive"))
      (node (ref "J1") (pin "324") (pinfunction "324_324") (pintype "passive"))
      (node (ref "J1") (pin "327") (pinfunction "327_327") (pintype "passive"))
      (node (ref "J1") (pin "330") (pinfunction "330_330") (pintype "passive"))
      (node (ref "J1") (pin "331") (pinfunction "331_331") (pintype "passive"))
      (node (ref "J1") (pin "334") (pinfunction "334_334") (pintype "passive"))
      (node (ref "J1") (pin "337") (pinfunction "337_337") (pintype "passive"))
      (node (ref "J1") (pin "34") (pinfunction "34_34") (pintype "passive"))
      (node (ref "J1") (pin "340") (pinfunction "340_340") (pintype "passive"))
      (node (ref "J1") (pin "341") (pinfunction "341_341") (pintype "passive"))
      (node (ref "J1") (pin "344") (pinfunction "344_344") (pintype "passive"))
      (node (ref "J1") (pin "347") (pinfunction "347_347") (pintype "passive"))
      (node (ref "J1") (pin "350") (pinfunction "350_350") (pintype "passive"))
      (node (ref "J1") (pin "351") (pinfunction "351_351") (pintype "passive"))
      (node (ref "J1") (pin "354") (pinfunction "354_354") (pintype "passive"))
      (node (ref "J1") (pin "357") (pinfunction "357_357") (pintype "passive"))
      (node (ref "J1") (pin "360") (pinfunction "360_360") (pintype "passive"))
      (node (ref "J1") (pin "361") (pinfunction "361_361") (pintype "passive"))
      (node (ref "J1") (pin "364") (pinfunction "364_364") (pintype "passive"))
      (node (ref "J1") (pin "367") (pinfunction "367_367") (pintype "passive"))
      (node (ref "J1") (pin "37") (pinfunction "37_37") (pintype "passive"))
      (node (ref "J1") (pin "370") (pinfunction "370_370") (pintype "passive"))
      (node (ref "J1") (pin "371") (pinfunction "371_371") (pintype "passive"))
      (node (ref "J1") (pin "374") (pinfunction "374_374") (pintype "passive"))
      (node (ref "J1") (pin "377") (pinfunction "377_377") (pintype "passive"))
      (node (ref "J1") (pin "380") (pinfunction "380_380") (pintype "passive"))
      (node (ref "J1") (pin "381") (pinfunction "381_381") (pintype "passive"))
      (node (ref "J1") (pin "384") (pinfunction "384_384") (pintype "passive"))
      (node (ref "J1") (pin "387") (pinfunction "387_387") (pintype "passive"))
      (node (ref "J1") (pin "390") (pinfunction "390_390") (pintype "passive"))
      (node (ref "J1") (pin "391") (pinfunction "391_391") (pintype "passive"))
      (node (ref "J1") (pin "394") (pinfunction "394_394") (pintype "passive"))
      (node (ref "J1") (pin "397") (pinfunction "397_397") (pintype "passive"))
      (node (ref "J1") (pin "4") (pinfunction "4_4") (pintype "passive"))
      (node (ref "J1") (pin "40") (pinfunction "40_40") (pintype "passive"))
      (node (ref "J1") (pin "400") (pinfunction "400_400") (pintype "passive"))
      (node (ref "J1") (pin "41") (pinfunction "41_41") (pintype "passive"))
      (node (ref "J1") (pin "44") (pinfunction "44_44") (pintype "passive"))
      (node (ref "J1") (pin "47") (pinfunction "47_47") (pintype "passive"))
      (node (ref "J1") (pin "50") (pinfunction "50_50") (pintype "passive"))
      (node (ref "J1") (pin "51") (pinfunction "51_51") (pintype "passive"))
      (node (ref "J1") (pin "54") (pinfunction "54_54") (pintype "passive"))
      (node (ref "J1") (pin "57") (pinfunction "57_57") (pintype "passive"))
      (node (ref "J1") (pin "60") (pinfunction "60_60") (pintype "passive"))
      (node (ref "J1") (pin "61") (pinfunction "61_61") (pintype "passive"))
      (node (ref "J1") (pin "64") (pinfunction "64_64") (pintype "passive"))
      (node (ref "J1") (pin "67") (pinfunction "67_67") (pintype "passive"))
      (node (ref "J1") (pin "7") (pinfunction "7_7") (pintype "passive"))
      (node (ref "J1") (pin "70") (pinfunction "70_70") (pintype "passive"))
      (node (ref "J1") (pin "71") (pinfunction "71_71") (pintype "passive"))
      (node (ref "J1") (pin "74") (pinfunction "74_74") (pintype "passive"))
      (node (ref "J1") (pin "77") (pinfunction "77_77") (pintype "passive"))
      (node (ref "J1") (pin "80") (pinfunction "80_80") (pintype "passive"))
      (node (ref "J1") (pin "81") (pinfunction "81_81") (pintype "passive"))
      (node (ref "J1") (pin "84") (pinfunction "84_84") (pintype "passive"))
      (node (ref "J1") (pin "87") (pinfunction "87_87") (pintype "passive"))
      (node (ref "J1") (pin "90") (pinfunction "90_90") (pintype "passive"))
      (node (ref "J1") (pin "91") (pinfunction "91_91") (pintype "passive"))
      (node (ref "J1") (pin "94") (pinfunction "94_94") (pintype "passive"))
      (node (ref "J1") (pin "97") (pinfunction "97_97") (pintype "passive"))
    )
    (net (code "188") (name "V1V35") (class "Default")
      (node (ref "R26") (pin "1") (pinfunction "1_1") (pintype "passive"))
      (node (ref "R27") (pin "1") (pinfunction "1_1") (pintype "passive"))
      (node (ref "R28") (pin "1") (pinfunction "1_1") (pintype "passive"))
    )
    (net (code "189") (name "V48") (class "Default")
      (node (ref "J1") (pin "225") (pinfunction "225_225") (pintype "passive"))
      (node (ref "J1") (pin "226") (pinfunction "226_226") (pintype "passive"))
      (node (ref "J1") (pin "228") (pinfunction "228_228") (pintype "passive"))
      (node (ref "J1") (pin "229") (pinfunction "229_229") (pintype "passive"))
      (node (ref "J1") (pin "232") (pinfunction "232_232") (pintype "passive"))
      (node (ref "J1") (pin "233") (pinfunction "233_233") (pintype "passive"))
      (node (ref "J1") (pin "235") (pinfunction "235_235") (pintype "passive"))
      (node (ref "J1") (pin "236") (pinfunction "236_236") (pintype "passive"))
      (node (ref "J1") (pin "238") (pinfunction "238_238") (pintype "passive"))
      (node (ref "J1") (pin "239") (pinfunction "239_239") (pintype "passive"))
      (node (ref "J1") (pin "242") (pinfunction "242_242") (pintype "passive"))
      (node (ref "J1") (pin "243") (pinfunction "243_243") (pintype "passive"))
      (node (ref "J1") (pin "245") (pinfunction "245_245") (pintype "passive"))
      (node (ref "J1") (pin "246") (pinfunction "246_246") (pintype "passive"))
      (node (ref "J1") (pin "248") (pinfunction "248_248") (pintype "passive"))
      (node (ref "J1") (pin "249") (pinfunction "249_249") (pintype "passive"))
    )
    (net (code "190") (name "VTTR") (class "Default")
      (node (ref "R25") (pin "1") (pinfunction "1_1") (pintype "passive"))
    )
    (net (code "191") (name "unconnected-(J1-Pad99)") (class "Default")
      (node (ref "J1") (pin "99") (pinfunction "99_99") (pintype "passive+no_connect"))
    )
    (net (code "192") (name "unconnected-(J1-Pad122)") (class "Default")
      (node (ref "J1") (pin "122") (pinfunction "122_122") (pintype "passive+no_connect"))
    )
    (net (code "193") (name "unconnected-(J1-Pad123)") (class "Default")
      (node (ref "J1") (pin "123") (pinfunction "123_123") (pintype "passive+no_connect"))
    )
    (net (code "194") (name "unconnected-(J1-Pad125)") (class "Default")
      (node (ref "J1") (pin "125") (pinfunction "125_125") (pintype "passive+no_connect"))
    )
    (net (code "195") (name "unconnected-(J1-Pad126)") (class "Default")
      (node (ref "J1") (pin "126") (pinfunction "126_126") (pintype "passive+no_connect"))
    )
    (net (code "196") (name "unconnected-(J1-Pad128)") (class "Default")
      (node (ref "J1") (pin "128") (pinfunction "128_128") (pintype "passive+no_connect"))
    )
    (net (code "197") (name "unconnected-(J1-Pad129)") (class "Default")
      (node (ref "J1") (pin "129") (pinfunction "129_129") (pintype "passive+no_connect"))
    )
    (net (code "198") (name "unconnected-(J1-Pad132)") (class "Default")
      (node (ref "J1") (pin "132") (pinfunction "132_132") (pintype "passive+no_connect"))
    )
    (net (code "199") (name "unconnected-(J1-Pad133)") (class "Default")
      (node (ref "J1") (pin "133") (pinfunction "133_133") (pintype "passive+no_connect"))
    )
    (net (code "200") (name "unconnected-(J1-Pad135)") (class "Default")
      (node (ref "J1") (pin "135") (pinfunction "135_135") (pintype "passive+no_connect"))
    )
    (net (code "201") (name "unconnected-(J1-Pad136)") (class "Default")
      (node (ref "J1") (pin "136") (pinfunction "136_136") (pintype "passive+no_connect"))
    )
    (net (code "202") (name "unconnected-(J1-Pad138)") (class "Default")
      (node (ref "J1") (pin "138") (pinfunction "138_138") (pintype "passive+no_connect"))
    )
    (net (code "203") (name "unconnected-(J1-Pad139)") (class "Default")
      (node (ref "J1") (pin "139") (pinfunction "139_139") (pintype "passive+no_connect"))
    )
    (net (code "204") (name "unconnected-(J1-Pad142)") (class "Default")
      (node (ref "J1") (pin "142") (pinfunction "142_142") (pintype "passive+no_connect"))
    )
    (net (code "205") (name "unconnected-(J1-Pad143)") (class "Default")
      (node (ref "J1") (pin "143") (pinfunction "143_143") (pintype "passive+no_connect"))
    )
    (net (code "206") (name "unconnected-(J1-Pad145)") (class "Default")
      (node (ref "J1") (pin "145") (pinfunction "145_145") (pintype "passive+no_connect"))
    )
    (net (code "207") (name "unconnected-(J1-Pad146)") (class "Default")
      (node (ref "J1") (pin "146") (pinfunction "146_146") (pintype "passive+no_connect"))
    )
    (net (code "208") (name "unconnected-(J1-Pad148)") (class "Default")
      (node (ref "J1") (pin "148") (pinfunction "148_148") (pintype "passive+no_connect"))
    )
    (net (code "209") (name "unconnected-(J1-Pad149)") (class "Default")
      (node (ref "J1") (pin "149") (pinfunction "149_149") (pintype "passive+no_connect"))
    )
    (net (code "210") (name "unconnected-(J1-Pad212)") (class "Default")
      (node (ref "J1") (pin "212") (pinfunction "212_212") (pintype "passive"))
    )
    (net (code "211") (name "unconnected-(J1-Pad213)") (class "Default")
      (node (ref "J1") (pin "213") (pinfunction "213_213") (pintype "passive"))
    )
    (net (code "212") (name "unconnected-(J1-Pad215)") (class "Default")
      (node (ref "J1") (pin "215") (pinfunction "215_215") (pintype "passive"))
    )
    (net (code "213") (name "unconnected-(J1-Pad216)") (class "Default")
      (node (ref "J1") (pin "216") (pinfunction "216_216") (pintype "passive"))
    )
    (net (code "214") (name "unconnected-(J1-Pad299)") (class "Default")
      (node (ref "J1") (pin "299") (pinfunction "299_299") (pintype "passive+no_connect"))
    )
  )
)
